# AST1045.net
KiCad netlist of a schematic drawn in EAGLE
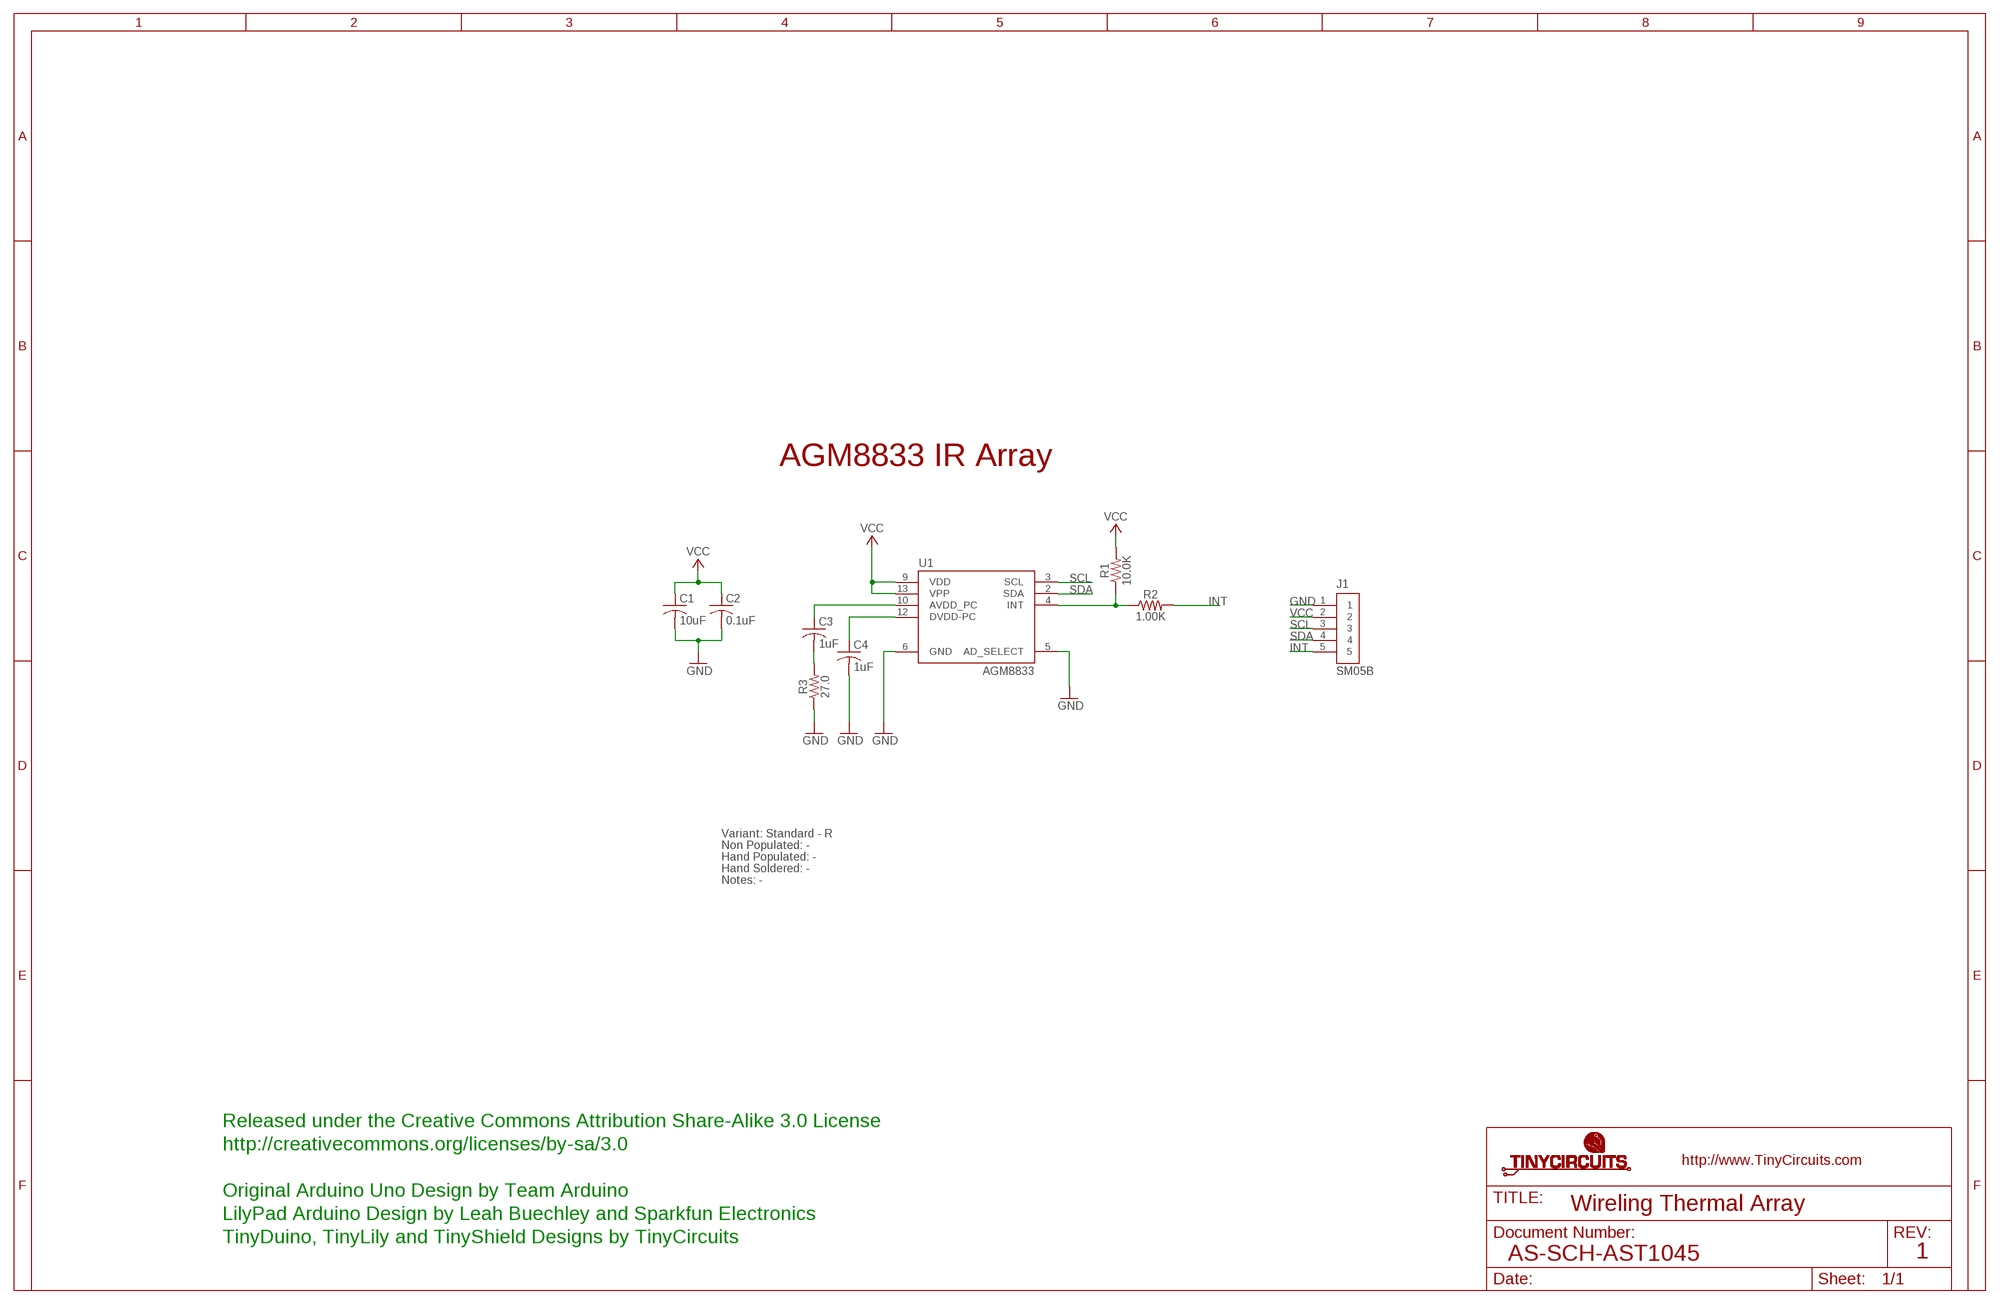
[diagram p0: schematic, sheet 1]

(export (version "E")
  (design (tool "Eeschema 10.0.6"))
  (components
    (comp (ref "C1")
      (value "10uF")
      (footprint "eagle-import:C0603")
      (fields (field (name "PARTNO") "AS-ITM-00002"))
      (libsource (lib "eagle-import") (part "AS-ITM-00002"))
    )
    (comp (ref "C2")
      (value "0.1uF")
      (footprint "eagle-import:C0402")
      (fields (field (name "PARTNO") "AS-ITM-00008"))
      (libsource (lib "eagle-import") (part "AS-ITM-00008"))
    )
    (comp (ref "C3")
      (value "1uF")
      (footprint "eagle-import:C0402")
      (fields (field (name "PARTNO") "AS-ITM-00105"))
      (libsource (lib "eagle-import") (part "AS-ITM-00105"))
    )
    (comp (ref "C4")
      (value "1uF")
      (footprint "eagle-import:C0402")
      (fields (field (name "PARTNO") "AS-ITM-00105") (field (name "PARTNO_1") "AS-ITM-00105"))
      (libsource (lib "eagle-import") (part "AS-ITM-00105"))
    )
    (comp (ref "J1")
      (value "SM05B")
      (footprint "eagle-import:JST_SH_5X1")
      (fields (field (name "PARTNO") "AS-ITM-00340"))
      (libsource (lib "eagle-import") (part "AS-ITM-00340"))
    )
    (comp (ref "R1")
      (value "10.0K")
      (footprint "eagle-import:0402")
      (fields (field (name "PARTNO") "AS-ITM-00032") (field (name "PARTNO_1") "AS-ITM-00032"))
      (libsource (lib "eagle-import") (part "AS-ITM-00032"))
    )
    (comp (ref "R2")
      (value "1.00K")
      (footprint "eagle-import:0402")
      (fields (field (name "PARTNO") "AS-ITM-00003") (field (name "PARTNO_1") "AS-ITM-00003"))
      (libsource (lib "eagle-import") (part "AS-ITM-00003"))
    )
    (comp (ref "R3")
      (value "27.0")
      (footprint "eagle-import:0402")
      (fields (field (name "PARTNO") "AS-ITM-00240"))
      (libsource (lib "eagle-import") (part "AS-ITM-00240"))
    )
    (comp (ref "U1")
      (value "AGM8833")
      (footprint "eagle-import:AMG8833")
      (fields (field (name "PARTNO") "AS-ITM-00545"))
      (libsource (lib "eagle-import") (part "AS-ITM-00545"))
    )
  )
  (nets
    (net (code "1") (name "/INT") (class "Default")
      (node (ref "J1") (pin "5") (pinfunction "5_5") (pintype "bidirectional"))
      (node (ref "R2") (pin "2") (pinfunction "2_2") (pintype "passive"))
    )
    (net (code "2") (name "/SCL") (class "Default")
      (node (ref "J1") (pin "3") (pinfunction "3_3") (pintype "bidirectional"))
      (node (ref "U1") (pin "3") (pinfunction "SCL_3") (pintype "bidirectional"))
    )
    (net (code "3") (name "/SDA") (class "Default")
      (node (ref "J1") (pin "4") (pinfunction "4_4") (pintype "bidirectional"))
      (node (ref "U1") (pin "2") (pinfunction "SDA_2") (pintype "bidirectional"))
    )
    (net (code "4") (name "GND") (class "Default")
      (node (ref "C1") (pin "2") (pinfunction "2_2") (pintype "passive"))
      (node (ref "C2") (pin "2") (pinfunction "2_2") (pintype "passive"))
      (node (ref "C4") (pin "2") (pinfunction "2_2") (pintype "passive"))
      (node (ref "J1") (pin "1") (pinfunction "1_1") (pintype "bidirectional"))
      (node (ref "R3") (pin "1") (pinfunction "1_1") (pintype "passive"))
      (node (ref "U1") (pin "5") (pinfunction "AD_SELECT_5") (pintype "bidirectional"))
      (node (ref "U1") (pin "6") (pinfunction "GND_6") (pintype "bidirectional"))
    )
    (net (code "5") (name "Net-(C3-Pad2)") (class "Default")
      (node (ref "C3") (pin "2") (pinfunction "2_2") (pintype "passive"))
      (node (ref "R3") (pin "2") (pinfunction "2_2") (pintype "passive"))
    )
    (net (code "6") (name "Net-(U1-AVDD_PC)") (class "Default")
      (node (ref "C3") (pin "1") (pinfunction "1_1") (pintype "passive"))
      (node (ref "U1") (pin "10") (pinfunction "AVDD_PC_10") (pintype "bidirectional"))
    )
    (net (code "7") (name "Net-(U1-DVDD-PC)") (class "Default")
      (node (ref "C4") (pin "1") (pinfunction "1_1") (pintype "passive"))
      (node (ref "U1") (pin "12") (pinfunction "DVDD-PC_12") (pintype "bidirectional"))
    )
    (net (code "8") (name "Net-(U1-INT)") (class "Default")
      (node (ref "R1") (pin "1") (pinfunction "1_1") (pintype "passive"))
      (node (ref "R2") (pin "1") (pinfunction "1_1") (pintype "passive"))
      (node (ref "U1") (pin "4") (pinfunction "INT_4") (pintype "bidirectional"))
    )
    (net (code "9") (name "VCC") (class "Default")
      (node (ref "C1") (pin "1") (pinfunction "1_1") (pintype "passive"))
      (node (ref "C2") (pin "1") (pinfunction "1_1") (pintype "passive"))
      (node (ref "J1") (pin "2") (pinfunction "2_2") (pintype "bidirectional"))
      (node (ref "R1") (pin "2") (pinfunction "2_2") (pintype "passive"))
      (node (ref "U1") (pin "13") (pinfunction "VPP_13") (pintype "bidirectional"))
      (node (ref "U1") (pin "9") (pinfunction "VDD_9") (pintype "bidirectional"))
    )
  )
)
